# Memory.net
KiCad netlist of a schematic drawn in Altium Designer
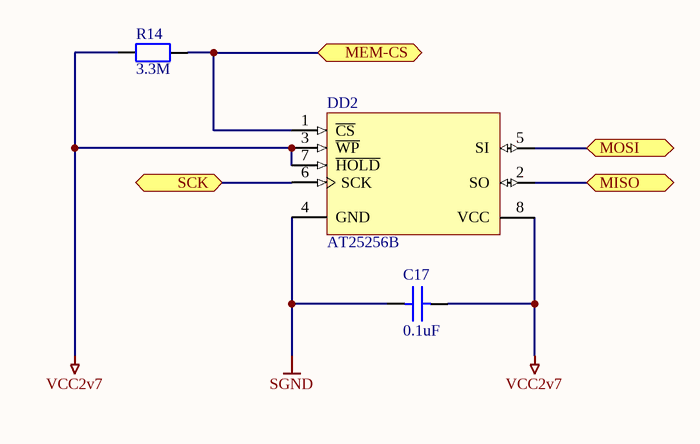
[diagram p0: Memory.SchDoc]

(export (version "E")
  (design (tool "Eeschema 10.0.6"))
  (components
    (comp (ref "C17")
      (value "0.1uF")
      (footprint "C0805")
      (description "C0.1uF-50V")
      (fields (field (name "VOLTAGE") "50V"))
      (libsource (lib "MCounter_Common") (part "C0.1uF-50V"))
    )
    (comp (ref "DD2")
      (value "AT25256B")
      (footprint "8S12_UNIV")
      (description "SPI Serial EEPROM 256K Memory")
      (libsource (lib "MCounter_Common") (part "AT25256B"))
    )
    (comp (ref "R14")
      (value "3.3M")
      (footprint "R0805")
      (description "R3.3M-5%")
      (libsource (lib "MCounter_Common") (part "R3.3M-5%"))
    )
  )
  (nets
    (net (code "1") (name "/MEM-CS") (class "Default")
      (node (ref "DD2") (pin "1") (pinfunction "~{CS}_1") (pintype "input"))
      (node (ref "R14") (pin "2") (pinfunction "2_2") (pintype "passive"))
    )
    (net (code "2") (name "/MISO") (class "Default")
      (node (ref "DD2") (pin "2") (pinfunction "SO_2") (pintype "bidirectional"))
    )
    (net (code "3") (name "/MOSI") (class "Default")
      (node (ref "DD2") (pin "5") (pinfunction "SI_5") (pintype "bidirectional"))
    )
    (net (code "4") (name "/SCK") (class "Default")
      (node (ref "DD2") (pin "6") (pinfunction "SCK_6") (pintype "input"))
    )
    (net (code "5") (name "SGND") (class "Default")
      (node (ref "C17") (pin "1") (pinfunction "1_1") (pintype "passive"))
      (node (ref "DD2") (pin "4") (pinfunction "GND_4") (pintype "power_in"))
    )
    (net (code "6") (name "VCC2v7") (class "Default")
      (node (ref "C17") (pin "2") (pinfunction "2_2") (pintype "passive"))
      (node (ref "DD2") (pin "3") (pinfunction "~{WP}_3") (pintype "input"))
      (node (ref "DD2") (pin "7") (pinfunction "~{HOLD}_7") (pintype "input"))
      (node (ref "DD2") (pin "8") (pinfunction "VCC_8") (pintype "power_in"))
      (node (ref "R14") (pin "1") (pinfunction "1_1") (pintype "passive"))
    )
  )
)
